# UpstreamPort.net
KiCad netlist of a schematic drawn in Altium Designer
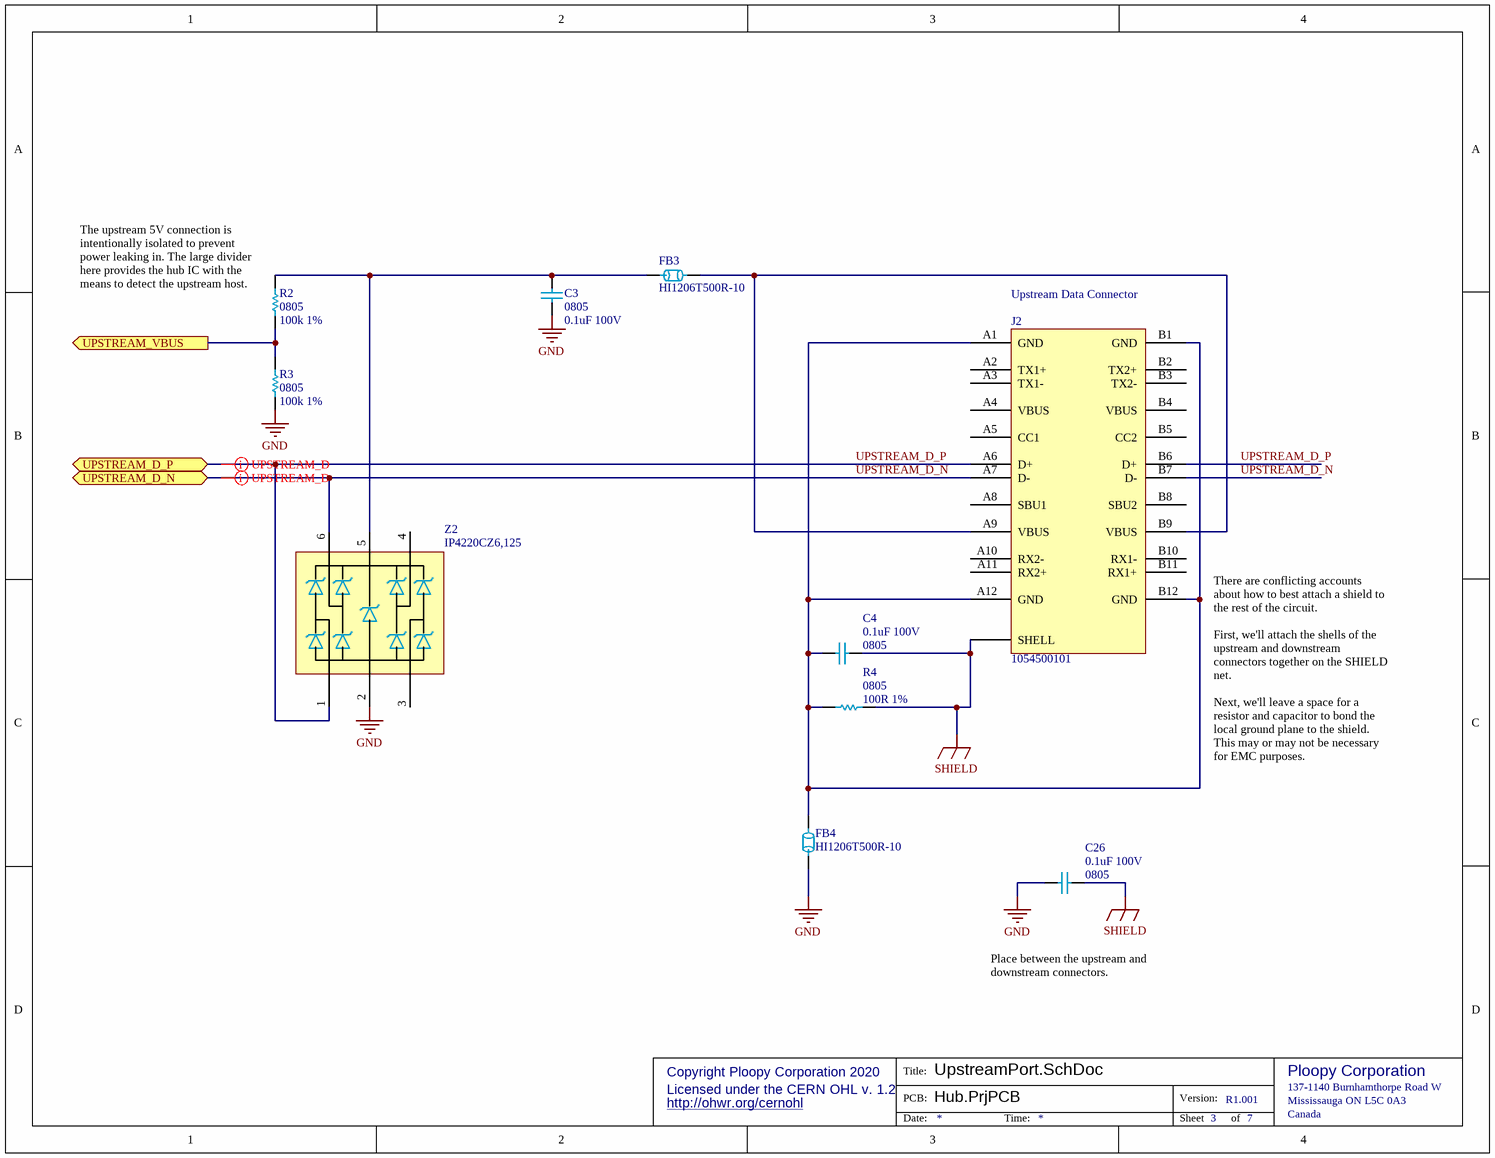
[diagram p0: UpstreamPort.SchDoc]

(export (version "E")
  (design (tool "Eeschema 10.0.6"))
  (components
    (comp (ref "C3")
      (value "0805")
      (footprint "0805")
      (description "0805, X5R or better")
      (fields (field (name "ALTIUM_VALUE") "0.1uF 100V"))
      (libsource (lib "Chip_Passives") (part "Cap 0.1uF 100V"))
    )
    (comp (ref "C4")
      (value "0805")
      (footprint "0805")
      (description "0805, X5R or better")
      (fields (field (name "ALTIUM_VALUE") "0.1uF 100V"))
      (libsource (lib "Chip_Passives") (part "Cap 0.1uF 100V"))
    )
    (comp (ref "C26")
      (value "0805")
      (footprint "0805")
      (description "0805, X5R or better")
      (fields (field (name "ALTIUM_VALUE") "0.1uF 100V"))
      (libsource (lib "Chip_Passives") (part "Cap 0.1uF 100V"))
    )
    (comp (ref "FB3")
      (value "HI1206T500R-10")
      (footprint "1206")
      (description "50 Ohms @ 100MHz 1 Power, Signal Line Ferrite Bead 1206 (3216 Metric) 6A 10mOhm")
      (libsource (lib "Chip_Passives") (part "HI1206T500R-10"))
    )
    (comp (ref "FB4")
      (value "HI1206T500R-10")
      (footprint "1206")
      (description "50 Ohms @ 100MHz 1 Power, Signal Line Ferrite Bead 1206 (3216 Metric) 6A 10mOhm")
      (libsource (lib "Chip_Passives") (part "HI1206T500R-10"))
    )
    (comp (ref "J2")
      (value "1054500101")
      (footprint "1054500101")
      (libsource (lib "Connectors") (part "1054500101"))
    )
    (comp (ref "R2")
      (value "0805")
      (footprint "0805")
      (description "Chip resistor")
      (fields (field (name "ALTIUM_VALUE") "100k 1%"))
      (libsource (lib "Chip_Passives") (part "Res 100k 1% 0805"))
    )
    (comp (ref "R3")
      (value "0805")
      (footprint "0805")
      (description "Chip resistor")
      (fields (field (name "ALTIUM_VALUE") "100k 1%"))
      (libsource (lib "Chip_Passives") (part "Res 100k 1% 0805"))
    )
    (comp (ref "R4")
      (value "0805")
      (footprint "0805")
      (description "Chip resistor")
      (fields (field (name "ALTIUM_VALUE") "100R 1%"))
      (libsource (lib "Chip_Passives") (part "Res 100R 1% 0805"))
    )
    (comp (ref "Z2")
      (value "IP4220CZ6,125")
      (footprint "PESD3V3S4UD - SOT95P275X110-6N")
      (description "TVS DIODE 5.5V 6TSOP (Low capacitance, USB)")
      (libsource (lib "Diodes") (part "IP4220CZ6,125"))
    )
  )
  (nets
    (net (code "1") (name "/UPSTREAM_D_N") (class "Default")
      (node (ref "J2") (pin "A7") (pinfunction "D-_A7") (pintype "passive"))
      (node (ref "J2") (pin "B7") (pinfunction "D-_B7") (pintype "passive"))
      (node (ref "Z2") (pin "6") (pinfunction "6_6") (pintype "passive"))
    )
    (net (code "2") (name "/UPSTREAM_D_P") (class "Default")
      (node (ref "J2") (pin "A6") (pinfunction "D+_A6") (pintype "passive"))
      (node (ref "J2") (pin "B6") (pinfunction "D+_B6") (pintype "passive"))
      (node (ref "Z2") (pin "1") (pinfunction "1_1") (pintype "passive"))
    )
    (net (code "3") (name "/UPSTREAM_VBUS") (class "Default")
      (node (ref "R2") (pin "1") (pinfunction "1_1") (pintype "passive"))
      (node (ref "R3") (pin "2") (pinfunction "2_2") (pintype "passive"))
    )
    (net (code "4") (name "GND") (class "Default")
      (node (ref "C26") (pin "1") (pinfunction "1_1") (pintype "passive"))
      (node (ref "C3") (pin "1") (pinfunction "1_1") (pintype "passive"))
      (node (ref "FB4") (pin "1") (pinfunction "1_1") (pintype "passive"))
      (node (ref "R3") (pin "1") (pinfunction "1_1") (pintype "passive"))
      (node (ref "Z2") (pin "2") (pinfunction "2_2") (pintype "passive"))
    )
    (net (code "5") (name "Net-(C3-Pad2)") (class "Default")
      (node (ref "C3") (pin "2") (pinfunction "2_2") (pintype "passive"))
      (node (ref "FB3") (pin "1") (pinfunction "1_1") (pintype "passive"))
      (node (ref "R2") (pin "2") (pinfunction "2_2") (pintype "passive"))
      (node (ref "Z2") (pin "5") (pinfunction "5_5") (pintype "passive"))
    )
    (net (code "6") (name "Net-(C4-Pad1)") (class "Default")
      (node (ref "C4") (pin "1") (pinfunction "1_1") (pintype "passive"))
      (node (ref "FB4") (pin "2") (pinfunction "2_2") (pintype "passive"))
      (node (ref "J2") (pin "A1") (pinfunction "GND_A1") (pintype "passive"))
      (node (ref "J2") (pin "A12") (pinfunction "GND_A12") (pintype "passive"))
      (node (ref "J2") (pin "B1") (pinfunction "GND_B1") (pintype "passive"))
      (node (ref "J2") (pin "B12") (pinfunction "GND_B12") (pintype "passive"))
      (node (ref "R4") (pin "1") (pinfunction "1_1") (pintype "passive"))
    )
    (net (code "7") (name "Net-(FB3-Pad2)") (class "Default")
      (node (ref "FB3") (pin "2") (pinfunction "2_2") (pintype "passive"))
      (node (ref "J2") (pin "A9") (pinfunction "VBUS_A9") (pintype "passive"))
      (node (ref "J2") (pin "B9") (pinfunction "VBUS_B9") (pintype "passive"))
    )
    (net (code "8") (name "SHIELD") (class "Default")
      (node (ref "C26") (pin "2") (pinfunction "2_2") (pintype "passive"))
      (node (ref "C4") (pin "2") (pinfunction "2_2") (pintype "passive"))
      (node (ref "J2") (pin "SHELL") (pinfunction "SHELL_SHELL") (pintype "passive"))
      (node (ref "R4") (pin "2") (pinfunction "2_2") (pintype "passive"))
    )
    (net (code "9") (name "unconnected-(J2-CC1-PadA5)") (class "Default")
      (node (ref "J2") (pin "A5") (pinfunction "CC1_A5") (pintype "passive"))
    )
    (net (code "10") (name "unconnected-(J2-CC2-PadB5)") (class "Default")
      (node (ref "J2") (pin "B5") (pinfunction "CC2_B5") (pintype "passive"))
    )
    (net (code "11") (name "unconnected-(J2-RX1+-PadB11)") (class "Default")
      (node (ref "J2") (pin "B11") (pinfunction "RX1+_B11") (pintype "passive"))
    )
    (net (code "12") (name "unconnected-(J2-RX1--PadB10)") (class "Default")
      (node (ref "J2") (pin "B10") (pinfunction "RX1-_B10") (pintype "passive"))
    )
    (net (code "13") (name "unconnected-(J2-RX2+-PadA11)") (class "Default")
      (node (ref "J2") (pin "A11") (pinfunction "RX2+_A11") (pintype "passive"))
    )
    (net (code "14") (name "unconnected-(J2-RX2--PadA10)") (class "Default")
      (node (ref "J2") (pin "A10") (pinfunction "RX2-_A10") (pintype "passive"))
    )
    (net (code "15") (name "unconnected-(J2-SBU1-PadA8)") (class "Default")
      (node (ref "J2") (pin "A8") (pinfunction "SBU1_A8") (pintype "passive"))
    )
    (net (code "16") (name "unconnected-(J2-SBU2-PadB8)") (class "Default")
      (node (ref "J2") (pin "B8") (pinfunction "SBU2_B8") (pintype "passive"))
    )
    (net (code "17") (name "unconnected-(J2-TX1+-PadA2)") (class "Default")
      (node (ref "J2") (pin "A2") (pinfunction "TX1+_A2") (pintype "passive"))
    )
    (net (code "18") (name "unconnected-(J2-TX1--PadA3)") (class "Default")
      (node (ref "J2") (pin "A3") (pinfunction "TX1-_A3") (pintype "passive"))
    )
    (net (code "19") (name "unconnected-(J2-TX2+-PadB2)") (class "Default")
      (node (ref "J2") (pin "B2") (pinfunction "TX2+_B2") (pintype "passive"))
    )
    (net (code "20") (name "unconnected-(J2-TX2--PadB3)") (class "Default")
      (node (ref "J2") (pin "B3") (pinfunction "TX2-_B3") (pintype "passive"))
    )
    (net (code "21") (name "unconnected-(J2-VBUS-PadA4)") (class "Default")
      (node (ref "J2") (pin "A4") (pinfunction "VBUS_A4") (pintype "passive"))
    )
    (net (code "22") (name "unconnected-(J2-VBUS-PadB4)") (class "Default")
      (node (ref "J2") (pin "B4") (pinfunction "VBUS_B4") (pintype "passive"))
    )
    (net (code "23") (name "unconnected-(Z2-Pad3)") (class "Default")
      (node (ref "Z2") (pin "3") (pinfunction "3_3") (pintype "passive"))
    )
    (net (code "24") (name "unconnected-(Z2-Pad4)") (class "Default")
      (node (ref "Z2") (pin "4") (pinfunction "4_4") (pintype "passive"))
    )
  )
)
